# Driver.net
KiCad netlist of a schematic drawn in Altium Designer
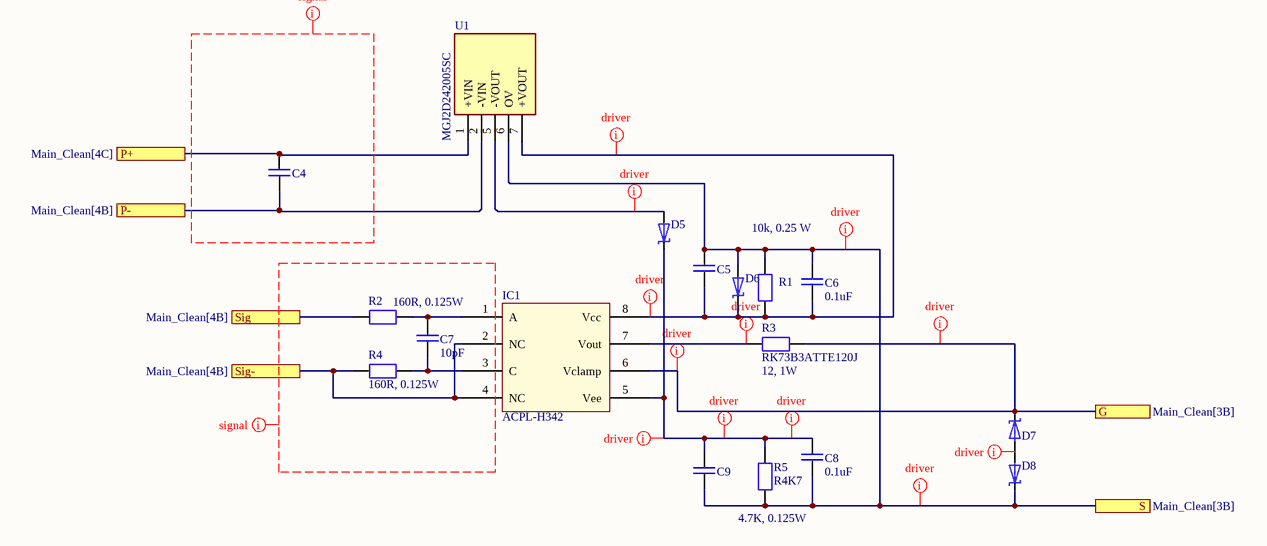
[diagram p0: Driver.SchDoc]

(export (version "E")
  (design (tool "Eeschema 10.0.6"))
  (components
    (comp (ref "C4")
      (value "Cer_large")
      (footprint "CAPC3227X25N")
      (libsource (lib "capacitors") (part "Cer_large"))
    )
    (comp (ref "C5")
      (value "Cer_large")
      (footprint "CAPC3227X25N")
      (libsource (lib "capacitors") (part "Cer_large"))
    )
    (comp (ref "C6")
      (value "0.1uF")
      (footprint "C_0805")
      (description "0.1u, 50V")
      (fields (field (name "MANUFACTURER") "Kemet") (field (name "Comment") "C0805C104K5RAC"))
      (libsource (lib "capacitors") (part "C0805C104K5RAC"))
    )
    (comp (ref "C7")
      (value "10pF")
      (footprint "C_0805")
      (description "10p, 100V")
      (fields (field (name "MANUFACTURER") "Kemet") (field (name "Comment") "C0805C100J1GAC"))
      (libsource (lib "capacitors") (part "C0805C100J1GAC"))
    )
    (comp (ref "C8")
      (value "0.1uF")
      (footprint "C_0805")
      (description "0.1u, 50V")
      (fields (field (name "MANUFACTURER") "Kemet") (field (name "Comment") "C0805C104K5RAC"))
      (libsource (lib "capacitors") (part "C0805C104K5RAC"))
    )
    (comp (ref "C9")
      (value "Cer_large")
      (footprint "CAPC3227X25N")
      (libsource (lib "capacitors") (part "Cer_large"))
    )
    (comp (ref "D5")
      (value "Zener_1.8V")
      (footprint "SOD123")
      (description "Zener diode")
      (libsource (lib "Library") (part "Zener_1.8V"))
    )
    (comp (ref "D6")
      (value "DZ2J220M0L")
      (footprint "SOD323F")
      (libsource (lib "Library") (part "DZ2J220M0L"))
    )
    (comp (ref "D7")
      (value "MMSZ4678T1G")
      (footprint "CAPM3216X18N")
      (description "6V, 500mW, Zener Diodes")
      (fields (field (name "MANUFACTURER") "ON Semiconductor") (field (name "PARTNUMBER") "MMSZ5233BT1G"))
      (libsource (lib "Universal_Control_Measure_Board") (part "Zener_MMSZ5233BT1G"))
    )
    (comp (ref "D8")
      (value "MMSZ4678T1G")
      (footprint "CAPM3216X18N")
      (description "6V, 500mW, Zener Diodes")
      (fields (field (name "MANUFACTURER") "ON Semiconductor") (field (name "PARTNUMBER") "MMSZ5233BT1G"))
      (libsource (lib "Universal_Control_Measure_Board") (part "Zener_MMSZ5233BT1G"))
    )
    (comp (ref "IC1")
      (value "ACPL-H342")
      (footprint "SOIC127P970X330-8N")
      (fields (field (name "MANUFACTURER") "Avago") (field (name "PUBLISHER") "*"))
      (libsource (lib "Schlib1") (part "ACPL-H342"))
    )
    (comp (ref "R1")
      (value "10k, 0.25 W")
      (footprint "SMD_1206")
      (fields (field (name "MANUFACTURER") "KOA") (field (name "Comment") "RK73H2BTTD1002F"))
      (libsource (lib "resistors") (part "RK73H2BTTD1002F"))
    )
    (comp (ref "R2")
      (value "160R, 0.125W")
      (footprint "SMD_0805")
      (fields (field (name "MANUFACTURER") "KOA") (field (name "Comment") "RK73H2ATTD1600F"))
      (libsource (lib "resistors") (part "RK73H2ATTD1600F"))
    )
    (comp (ref "R3")
      (value "RK73B3ATTE120J")
      (footprint "SMD_2512")
      (fields (field (name "MANUFACTURER") "KOA") (field (name "ALTIUM_VALUE") "12, 1W"))
      (libsource (lib "resistors") (part "RK73B3ATTE120J"))
    )
    (comp (ref "R4")
      (value "160R, 0.125W")
      (footprint "SMD_0805")
      (fields (field (name "MANUFACTURER") "KOA") (field (name "Comment") "RK73H2ATTD1600F"))
      (libsource (lib "resistors") (part "RK73H2ATTD1600F"))
    )
    (comp (ref "R5")
      (value "R4K7")
      (footprint "smd_0603")
      (fields (field (name "ALTIUM_VALUE") "4.7K, 0.125W"))
      (libsource (lib "resistors") (part "R4K7"))
    )
    (comp (ref "U1")
      (value "MGJ2D242005SC")
      (footprint "SamacSys:MURATA-MGJ2")
      (description "Undefined or Miscellaneous")
      (fields (field (name "MOUSER PART NUMBER") "580-MGJ2D242005SC"))
      (libsource (lib "SamacSys") (part "MGJ2D242005SC"))
    )
  )
  (nets
    (net (code "1") (name "/G") (class "Default")
      (node (ref "D7") (pin "1") (pinfunction "1_1") (pintype "passive"))
      (node (ref "IC1") (pin "6") (pinfunction "Vclamp_6") (pintype "passive"))
      (node (ref "R3") (pin "2") (pinfunction "2_2") (pintype "passive"))
    )
    (net (code "2") (name "/P+") (class "Default")
      (node (ref "C4") (pin "1") (pinfunction "1_1") (pintype "passive"))
      (node (ref "U1") (pin "1") (pinfunction "+VIN_1") (pintype "passive"))
    )
    (net (code "3") (name "/P-") (class "Default")
      (node (ref "C4") (pin "2") (pinfunction "2_2") (pintype "passive"))
      (node (ref "U1") (pin "2") (pinfunction "-VIN_2") (pintype "passive"))
    )
    (net (code "4") (name "/S") (class "Default")
      (node (ref "C5") (pin "1") (pinfunction "1_1") (pintype "passive"))
      (node (ref "C6") (pin "1") (pinfunction "1_1") (pintype "passive"))
      (node (ref "C8") (pin "2") (pinfunction "2_2") (pintype "passive"))
      (node (ref "C9") (pin "2") (pinfunction "2_2") (pintype "passive"))
      (node (ref "D6") (pin "1") (pinfunction "1_1") (pintype "passive"))
      (node (ref "D8") (pin "1") (pinfunction "1_1") (pintype "passive"))
      (node (ref "R1") (pin "2") (pinfunction "2_2") (pintype "passive"))
      (node (ref "R5") (pin "1") (pinfunction "1_1") (pintype "passive"))
      (node (ref "U1") (pin "6") (pinfunction "OV_6") (pintype "passive"))
    )
    (net (code "5") (name "/Sig") (class "Default")
      (node (ref "R2") (pin "1") (pinfunction "1_1") (pintype "passive"))
    )
    (net (code "6") (name "/Sig-") (class "Default")
      (node (ref "IC1") (pin "2") (pinfunction "NC_2") (pintype "passive"))
      (node (ref "IC1") (pin "4") (pinfunction "NC_4") (pintype "passive"))
      (node (ref "R4") (pin "1") (pinfunction "1_1") (pintype "passive"))
    )
    (net (code "7") (name "Net-(D7-Pad2)") (class "Default")
      (node (ref "D7") (pin "2") (pinfunction "2_2") (pintype "passive"))
      (node (ref "D8") (pin "2") (pinfunction "2_2") (pintype "passive"))
    )
    (net (code "8") (name "Net-(IC1-A)") (class "Default")
      (node (ref "C7") (pin "1") (pinfunction "1_1") (pintype "passive"))
      (node (ref "IC1") (pin "1") (pinfunction "A_1") (pintype "passive"))
      (node (ref "R2") (pin "2") (pinfunction "2_2") (pintype "passive"))
    )
    (net (code "9") (name "Net-(IC1-C)") (class "Default")
      (node (ref "C7") (pin "2") (pinfunction "2_2") (pintype "passive"))
      (node (ref "IC1") (pin "3") (pinfunction "C_3") (pintype "passive"))
      (node (ref "R4") (pin "2") (pinfunction "2_2") (pintype "passive"))
    )
    (net (code "10") (name "Net-(IC1-Vcc)") (class "Default")
      (node (ref "C5") (pin "2") (pinfunction "2_2") (pintype "passive"))
      (node (ref "C6") (pin "2") (pinfunction "2_2") (pintype "passive"))
      (node (ref "D6") (pin "2") (pinfunction "2_2") (pintype "passive"))
      (node (ref "IC1") (pin "8") (pinfunction "Vcc_8") (pintype "passive"))
      (node (ref "R1") (pin "1") (pinfunction "1_1") (pintype "passive"))
      (node (ref "U1") (pin "7") (pinfunction "+VOUT_7") (pintype "passive"))
    )
    (net (code "11") (name "Net-(IC1-Vee)") (class "Default")
      (node (ref "C8") (pin "1") (pinfunction "1_1") (pintype "passive"))
      (node (ref "C9") (pin "1") (pinfunction "1_1") (pintype "passive"))
      (node (ref "D5") (pin "2") (pinfunction "2_2") (pintype "passive"))
      (node (ref "IC1") (pin "5") (pinfunction "Vee_5") (pintype "passive"))
      (node (ref "R5") (pin "2") (pinfunction "2_2") (pintype "passive"))
    )
    (net (code "12") (name "Net-(IC1-Vout)") (class "Default")
      (node (ref "IC1") (pin "7") (pinfunction "Vout_7") (pintype "passive"))
      (node (ref "R3") (pin "1") (pinfunction "1_1") (pintype "passive"))
    )
    (net (code "13") (name "Net-(U1--VOUT)") (class "Default")
      (node (ref "D5") (pin "1") (pinfunction "1_1") (pintype "passive"))
      (node (ref "U1") (pin "5") (pinfunction "-VOUT_5") (pintype "passive"))
    )
  )
)
